# vidc_interposer1.net
KiCad netlist of a schematic drawn in EAGLE
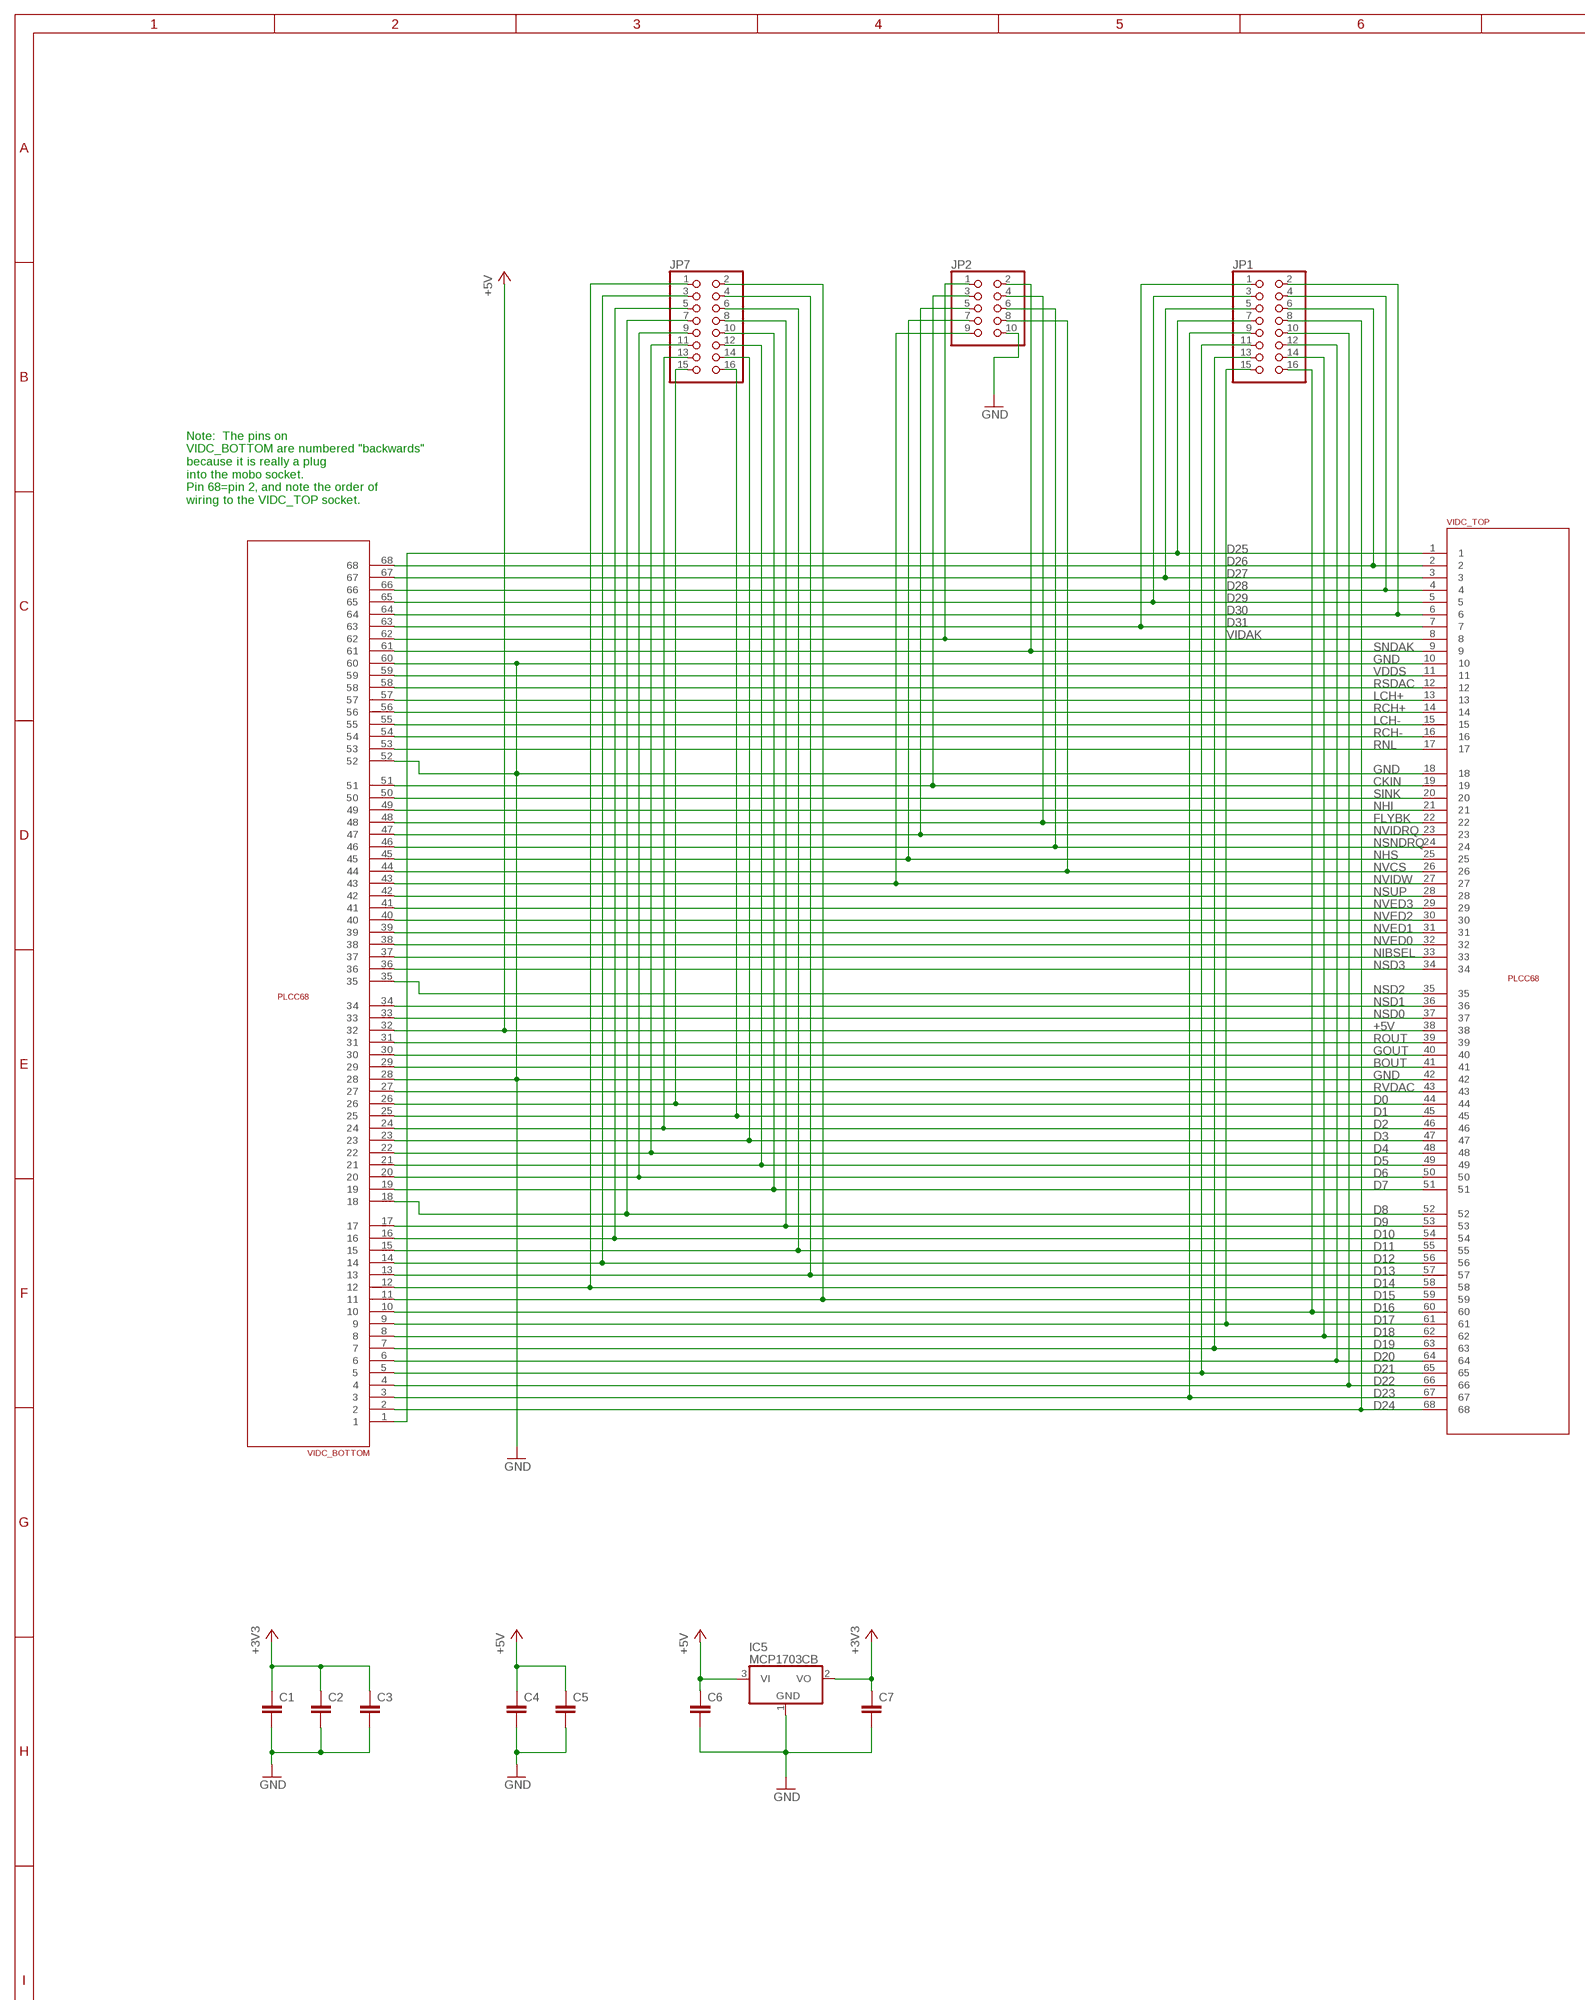
[diagram p0: schematic, sheet 1, part 1 of 2]
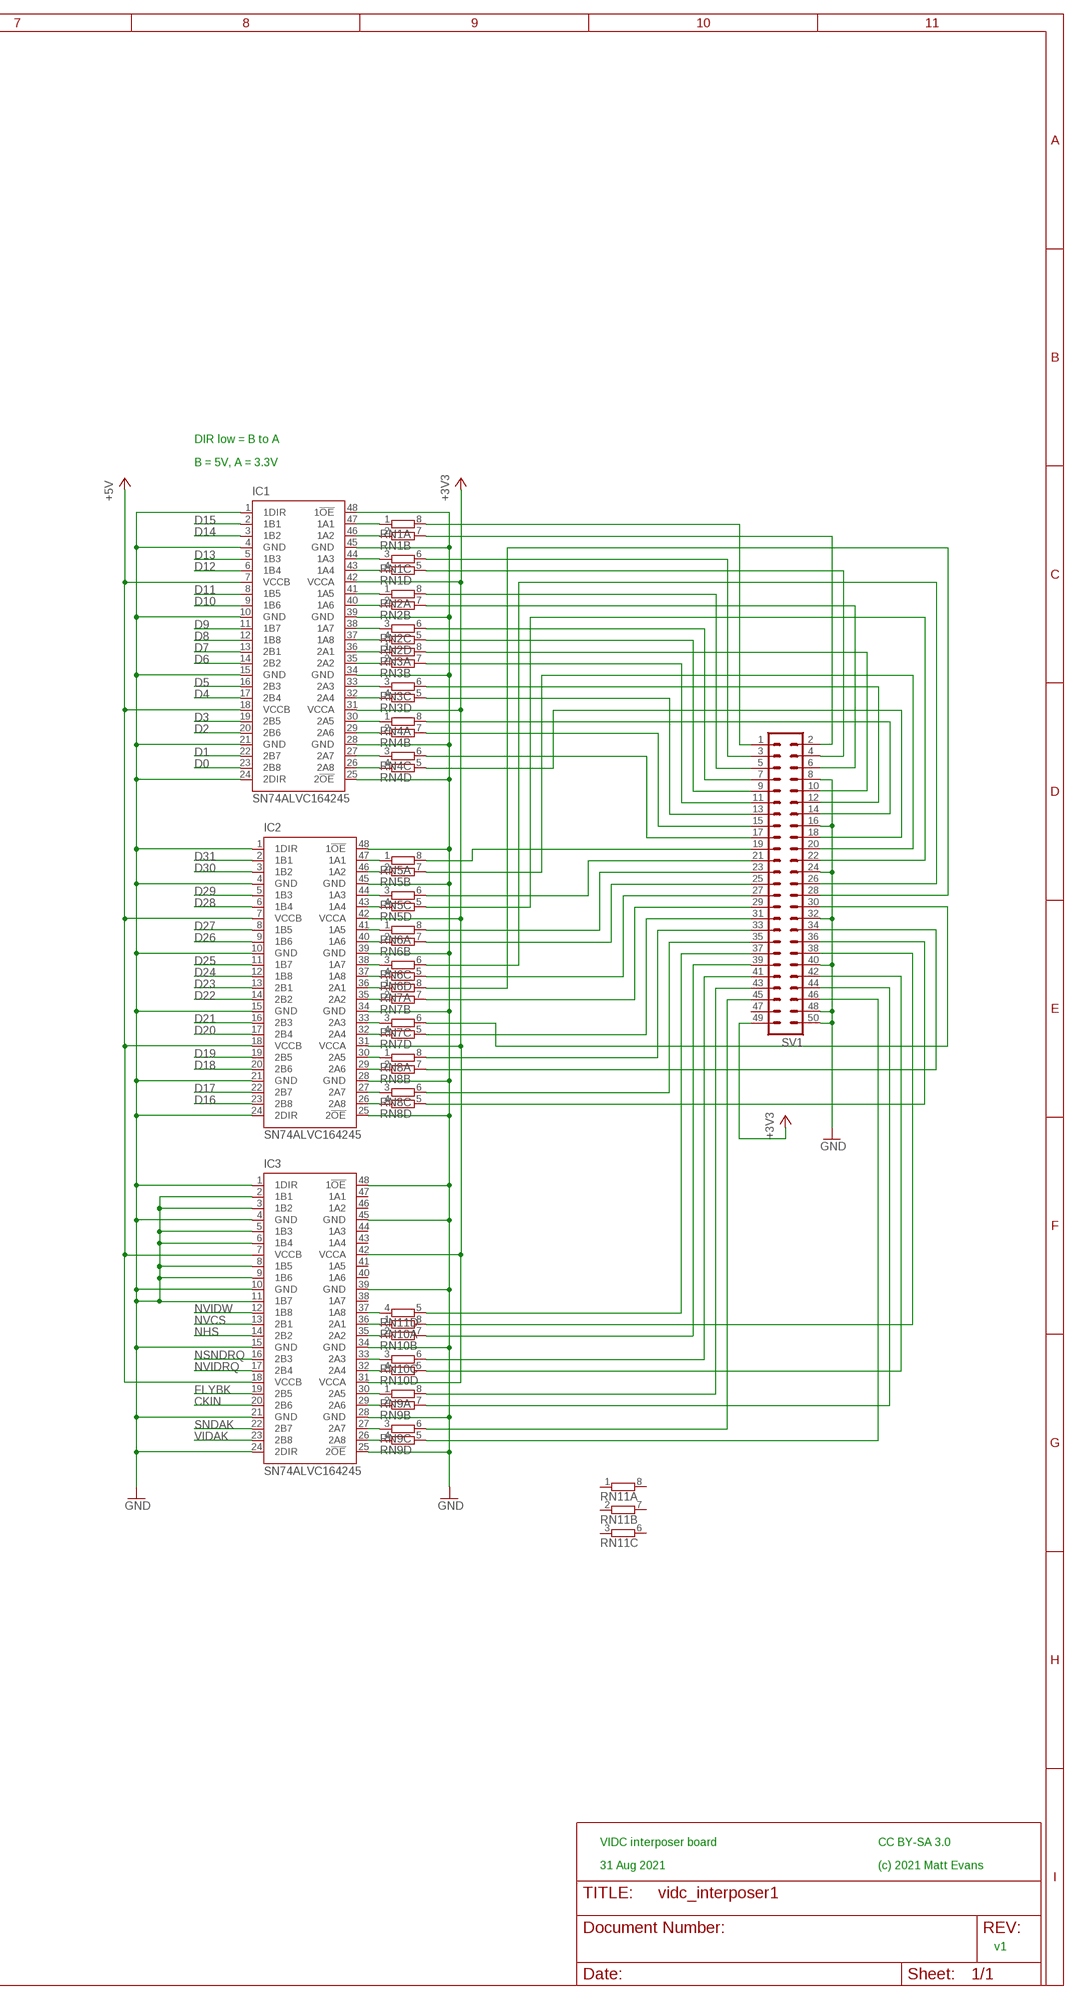
[diagram p1: schematic, sheet 1, part 2 of 2]

(export (version "E")
  (design (tool "Eeschema 10.0.6"))
  (components
    (comp (ref "C1")
      (value "C-EUC0805")
      (footprint "eagle-import:C0805")
      (libsource (lib "eagle-import") (part "C-EUC0805"))
    )
    (comp (ref "C2")
      (value "C-EUC0805")
      (footprint "eagle-import:C0805")
      (libsource (lib "eagle-import") (part "C-EUC0805"))
    )
    (comp (ref "C3")
      (value "C-EUC0805")
      (footprint "eagle-import:C0805")
      (libsource (lib "eagle-import") (part "C-EUC0805"))
    )
    (comp (ref "C4")
      (value "C-EUC0805")
      (footprint "eagle-import:C0805")
      (libsource (lib "eagle-import") (part "C-EUC0805"))
    )
    (comp (ref "C5")
      (value "C-EUC0805")
      (footprint "eagle-import:C0805")
      (libsource (lib "eagle-import") (part "C-EUC0805"))
    )
    (comp (ref "C6")
      (value "C-EUC0805")
      (footprint "eagle-import:C0805")
      (libsource (lib "eagle-import") (part "C-EUC0805"))
    )
    (comp (ref "C7")
      (value "C-EUC0805")
      (footprint "eagle-import:C0805")
      (libsource (lib "eagle-import") (part "C-EUC0805"))
    )
    (comp (ref "IC1")
      (value "SN74ALVC164245")
      (footprint "eagle-import:DL_R-PDSO-G48")
      (fields (field (name "MPN") "SN74LVCR162245DL"))
      (libsource (lib "eagle-import") (part "SN74ALVC164245"))
    )
    (comp (ref "IC2")
      (value "SN74ALVC164245")
      (footprint "eagle-import:DL_R-PDSO-G48")
      (fields (field (name "MPN") "SN74LVCR162245DL"))
      (libsource (lib "eagle-import") (part "SN74ALVC164245"))
    )
    (comp (ref "IC3")
      (value "SN74ALVC164245")
      (footprint "eagle-import:DL_R-PDSO-G48")
      (fields (field (name "MPN") "SN74LVCR162245DL"))
      (libsource (lib "eagle-import") (part "SN74ALVC164245"))
    )
    (comp (ref "IC5")
      (value "MCP1703CB")
      (footprint "eagle-import:SOT23")
      (libsource (lib "eagle-import") (part "MCP1703CB"))
    )
    (comp (ref "JP1")
      (value "PINHD-2X8")
      (footprint "eagle-import:2X08")
      (libsource (lib "eagle-import") (part "PINHD-2X8"))
    )
    (comp (ref "JP2")
      (value "PINHD-2X5")
      (footprint "eagle-import:2X05")
      (libsource (lib "eagle-import") (part "PINHD-2X5"))
    )
    (comp (ref "JP7")
      (value "PINHD-2X8")
      (footprint "eagle-import:2X08")
      (libsource (lib "eagle-import") (part "PINHD-2X8"))
    )
    (comp (ref "RN1")
      (value "4R-NCAY16")
      (footprint "eagle-import:CAY16")
      (libsource (lib "eagle-import") (part "4R-NCAY16"))
    )
    (comp (ref "RN2")
      (value "4R-NCAY16")
      (footprint "eagle-import:CAY16")
      (libsource (lib "eagle-import") (part "4R-NCAY16"))
    )
    (comp (ref "RN3")
      (value "4R-NCAY16")
      (footprint "eagle-import:CAY16")
      (libsource (lib "eagle-import") (part "4R-NCAY16"))
    )
    (comp (ref "RN4")
      (value "4R-NCAY16")
      (footprint "eagle-import:CAY16")
      (libsource (lib "eagle-import") (part "4R-NCAY16"))
    )
    (comp (ref "RN5")
      (value "4R-NCAY16")
      (footprint "eagle-import:CAY16")
      (libsource (lib "eagle-import") (part "4R-NCAY16"))
    )
    (comp (ref "RN6")
      (value "4R-NCAY16")
      (footprint "eagle-import:CAY16")
      (libsource (lib "eagle-import") (part "4R-NCAY16"))
    )
    (comp (ref "RN7")
      (value "4R-NCAY16")
      (footprint "eagle-import:CAY16")
      (libsource (lib "eagle-import") (part "4R-NCAY16"))
    )
    (comp (ref "RN8")
      (value "4R-NCAY16")
      (footprint "eagle-import:CAY16")
      (libsource (lib "eagle-import") (part "4R-NCAY16"))
    )
    (comp (ref "RN9")
      (value "4R-NCAY16")
      (footprint "eagle-import:CAY16")
      (libsource (lib "eagle-import") (part "4R-NCAY16"))
    )
    (comp (ref "RN10")
      (value "4R-NCAY16")
      (footprint "eagle-import:CAY16")
      (libsource (lib "eagle-import") (part "4R-NCAY16"))
    )
    (comp (ref "RN11")
      (value "4R-NCAY16")
      (footprint "eagle-import:CAY16")
      (libsource (lib "eagle-import") (part "4R-NCAY16"))
    )
    (comp (ref "SV1")
      (value "ML50")
      (footprint "eagle-import:ML50")
      (libsource (lib "eagle-import") (part "ML50"))
    )
    (comp (ref "VIDC_BOTTOM")
      (value "RAW_PLCC68")
      (footprint "eagle-import:PLCC68S")
      (libsource (lib "eagle-import") (part "RAW_PLCC68"))
    )
    (comp (ref "VIDC_TOP")
      (value "RAW_PLCC68")
      (footprint "eagle-import:PLCC68S")
      (libsource (lib "eagle-import") (part "RAW_PLCC68"))
    )
  )
  (nets
    (net (code "1") (name "+3V3") (class "Default")
      (node (ref "C1") (pin "1") (pinfunction "1_1") (pintype "passive"))
      (node (ref "C2") (pin "1") (pinfunction "1_1") (pintype "passive"))
      (node (ref "C3") (pin "1") (pinfunction "1_1") (pintype "passive"))
      (node (ref "C7") (pin "1") (pinfunction "1_1") (pintype "passive"))
      (node (ref "IC1") (pin "31") (pinfunction "VCCA_31") (pintype "power_in"))
      (node (ref "IC1") (pin "42") (pinfunction "VCCA_42") (pintype "power_in"))
      (node (ref "IC2") (pin "31") (pinfunction "VCCA_31") (pintype "power_in"))
      (node (ref "IC2") (pin "42") (pinfunction "VCCA_42") (pintype "power_in"))
      (node (ref "IC3") (pin "31") (pinfunction "VCCA_31") (pintype "power_in"))
      (node (ref "IC3") (pin "42") (pinfunction "VCCA_42") (pintype "power_in"))
      (node (ref "IC5") (pin "2") (pinfunction "VO_2") (pintype "passive"))
      (node (ref "SV1") (pin "49") (pinfunction "49_49") (pintype "passive"))
    )
    (net (code "2") (name "+5V") (class "Default")
      (node (ref "C4") (pin "1") (pinfunction "1_1") (pintype "passive"))
      (node (ref "C5") (pin "1") (pinfunction "1_1") (pintype "passive"))
      (node (ref "C6") (pin "1") (pinfunction "1_1") (pintype "passive"))
      (node (ref "IC1") (pin "18") (pinfunction "VCCB_18") (pintype "power_in"))
      (node (ref "IC1") (pin "7") (pinfunction "VCCB_7") (pintype "power_in"))
      (node (ref "IC2") (pin "18") (pinfunction "VCCB_18") (pintype "power_in"))
      (node (ref "IC2") (pin "7") (pinfunction "VCCB_7") (pintype "power_in"))
      (node (ref "IC3") (pin "18") (pinfunction "VCCB_18") (pintype "power_in"))
      (node (ref "IC3") (pin "7") (pinfunction "VCCB_7") (pintype "power_in"))
      (node (ref "IC5") (pin "3") (pinfunction "VI_3") (pintype "input"))
      (node (ref "VIDC_BOTTOM") (pin "32") (pinfunction "32_32") (pintype "bidirectional"))
      (node (ref "VIDC_TOP") (pin "38") (pinfunction "38_38") (pintype "bidirectional"))
    )
    (net (code "3") (name "/BOUT") (class "Default")
      (node (ref "VIDC_BOTTOM") (pin "29") (pinfunction "29_29") (pintype "bidirectional"))
      (node (ref "VIDC_TOP") (pin "41") (pinfunction "41_41") (pintype "bidirectional"))
    )
    (net (code "4") (name "/CKIN") (class "Default")
      (node (ref "IC3") (pin "20") (pinfunction "2B6_20") (pintype "tri_state"))
      (node (ref "JP2") (pin "3") (pinfunction "3_3") (pintype "passive"))
      (node (ref "VIDC_BOTTOM") (pin "51") (pinfunction "51_51") (pintype "bidirectional"))
      (node (ref "VIDC_TOP") (pin "19") (pinfunction "19_19") (pintype "bidirectional"))
    )
    (net (code "5") (name "/D0") (class "Default")
      (node (ref "IC1") (pin "23") (pinfunction "2B8_23") (pintype "tri_state"))
      (node (ref "JP7") (pin "15") (pinfunction "15_15") (pintype "passive"))
      (node (ref "VIDC_BOTTOM") (pin "26") (pinfunction "26_26") (pintype "bidirectional"))
      (node (ref "VIDC_TOP") (pin "44") (pinfunction "44_44") (pintype "bidirectional"))
    )
    (net (code "6") (name "/D1") (class "Default")
      (node (ref "IC1") (pin "22") (pinfunction "2B7_22") (pintype "tri_state"))
      (node (ref "JP7") (pin "16") (pinfunction "16_16") (pintype "passive"))
      (node (ref "VIDC_BOTTOM") (pin "25") (pinfunction "25_25") (pintype "bidirectional"))
      (node (ref "VIDC_TOP") (pin "45") (pinfunction "45_45") (pintype "bidirectional"))
    )
    (net (code "7") (name "/D2") (class "Default")
      (node (ref "IC1") (pin "20") (pinfunction "2B6_20") (pintype "tri_state"))
      (node (ref "JP7") (pin "13") (pinfunction "13_13") (pintype "passive"))
      (node (ref "VIDC_BOTTOM") (pin "24") (pinfunction "24_24") (pintype "bidirectional"))
      (node (ref "VIDC_TOP") (pin "46") (pinfunction "46_46") (pintype "bidirectional"))
    )
    (net (code "8") (name "/D3") (class "Default")
      (node (ref "IC1") (pin "19") (pinfunction "2B5_19") (pintype "tri_state"))
      (node (ref "JP7") (pin "14") (pinfunction "14_14") (pintype "passive"))
      (node (ref "VIDC_BOTTOM") (pin "23") (pinfunction "23_23") (pintype "bidirectional"))
      (node (ref "VIDC_TOP") (pin "47") (pinfunction "47_47") (pintype "bidirectional"))
    )
    (net (code "9") (name "/D4") (class "Default")
      (node (ref "IC1") (pin "17") (pinfunction "2B4_17") (pintype "tri_state"))
      (node (ref "JP7") (pin "11") (pinfunction "11_11") (pintype "passive"))
      (node (ref "VIDC_BOTTOM") (pin "22") (pinfunction "22_22") (pintype "bidirectional"))
      (node (ref "VIDC_TOP") (pin "48") (pinfunction "48_48") (pintype "bidirectional"))
    )
    (net (code "10") (name "/D5") (class "Default")
      (node (ref "IC1") (pin "16") (pinfunction "2B3_16") (pintype "tri_state"))
      (node (ref "JP7") (pin "12") (pinfunction "12_12") (pintype "passive"))
      (node (ref "VIDC_BOTTOM") (pin "21") (pinfunction "21_21") (pintype "bidirectional"))
      (node (ref "VIDC_TOP") (pin "49") (pinfunction "49_49") (pintype "bidirectional"))
    )
    (net (code "11") (name "/D6") (class "Default")
      (node (ref "IC1") (pin "14") (pinfunction "2B2_14") (pintype "tri_state"))
      (node (ref "JP7") (pin "9") (pinfunction "9_9") (pintype "passive"))
      (node (ref "VIDC_BOTTOM") (pin "20") (pinfunction "20_20") (pintype "bidirectional"))
      (node (ref "VIDC_TOP") (pin "50") (pinfunction "50_50") (pintype "bidirectional"))
    )
    (net (code "12") (name "/D7") (class "Default")
      (node (ref "IC1") (pin "13") (pinfunction "2B1_13") (pintype "tri_state"))
      (node (ref "JP7") (pin "10") (pinfunction "10_10") (pintype "passive"))
      (node (ref "VIDC_BOTTOM") (pin "19") (pinfunction "19_19") (pintype "bidirectional"))
      (node (ref "VIDC_TOP") (pin "51") (pinfunction "51_51") (pintype "bidirectional"))
    )
    (net (code "13") (name "/D8") (class "Default")
      (node (ref "IC1") (pin "12") (pinfunction "1B8_12") (pintype "tri_state"))
      (node (ref "JP7") (pin "7") (pinfunction "7_7") (pintype "passive"))
      (node (ref "VIDC_BOTTOM") (pin "18") (pinfunction "18_18") (pintype "bidirectional"))
      (node (ref "VIDC_TOP") (pin "52") (pinfunction "52_52") (pintype "bidirectional"))
    )
    (net (code "14") (name "/D9") (class "Default")
      (node (ref "IC1") (pin "11") (pinfunction "1B7_11") (pintype "tri_state"))
      (node (ref "JP7") (pin "8") (pinfunction "8_8") (pintype "passive"))
      (node (ref "VIDC_BOTTOM") (pin "17") (pinfunction "17_17") (pintype "bidirectional"))
      (node (ref "VIDC_TOP") (pin "53") (pinfunction "53_53") (pintype "bidirectional"))
    )
    (net (code "15") (name "/D10") (class "Default")
      (node (ref "IC1") (pin "9") (pinfunction "1B6_9") (pintype "tri_state"))
      (node (ref "JP7") (pin "5") (pinfunction "5_5") (pintype "passive"))
      (node (ref "VIDC_BOTTOM") (pin "16") (pinfunction "16_16") (pintype "bidirectional"))
      (node (ref "VIDC_TOP") (pin "54") (pinfunction "54_54") (pintype "bidirectional"))
    )
    (net (code "16") (name "/D11") (class "Default")
      (node (ref "IC1") (pin "8") (pinfunction "1B5_8") (pintype "tri_state"))
      (node (ref "JP7") (pin "6") (pinfunction "6_6") (pintype "passive"))
      (node (ref "VIDC_BOTTOM") (pin "15") (pinfunction "15_15") (pintype "bidirectional"))
      (node (ref "VIDC_TOP") (pin "55") (pinfunction "55_55") (pintype "bidirectional"))
    )
    (net (code "17") (name "/D12") (class "Default")
      (node (ref "IC1") (pin "6") (pinfunction "1B4_6") (pintype "tri_state"))
      (node (ref "JP7") (pin "3") (pinfunction "3_3") (pintype "passive"))
      (node (ref "VIDC_BOTTOM") (pin "14") (pinfunction "14_14") (pintype "bidirectional"))
      (node (ref "VIDC_TOP") (pin "56") (pinfunction "56_56") (pintype "bidirectional"))
    )
    (net (code "18") (name "/D13") (class "Default")
      (node (ref "IC1") (pin "5") (pinfunction "1B3_5") (pintype "tri_state"))
      (node (ref "JP7") (pin "4") (pinfunction "4_4") (pintype "passive"))
      (node (ref "VIDC_BOTTOM") (pin "13") (pinfunction "13_13") (pintype "bidirectional"))
      (node (ref "VIDC_TOP") (pin "57") (pinfunction "57_57") (pintype "bidirectional"))
    )
    (net (code "19") (name "/D14") (class "Default")
      (node (ref "IC1") (pin "3") (pinfunction "1B2_3") (pintype "tri_state"))
      (node (ref "JP7") (pin "1") (pinfunction "1_1") (pintype "passive"))
      (node (ref "VIDC_BOTTOM") (pin "12") (pinfunction "12_12") (pintype "bidirectional"))
      (node (ref "VIDC_TOP") (pin "58") (pinfunction "58_58") (pintype "bidirectional"))
    )
    (net (code "20") (name "/D15") (class "Default")
      (node (ref "IC1") (pin "2") (pinfunction "1B1_2") (pintype "tri_state"))
      (node (ref "JP7") (pin "2") (pinfunction "2_2") (pintype "passive"))
      (node (ref "VIDC_BOTTOM") (pin "11") (pinfunction "11_11") (pintype "bidirectional"))
      (node (ref "VIDC_TOP") (pin "59") (pinfunction "59_59") (pintype "bidirectional"))
    )
    (net (code "21") (name "/D16") (class "Default")
      (node (ref "IC2") (pin "23") (pinfunction "2B8_23") (pintype "tri_state"))
      (node (ref "JP1") (pin "16") (pinfunction "16_16") (pintype "passive"))
      (node (ref "VIDC_BOTTOM") (pin "10") (pinfunction "10_10") (pintype "bidirectional"))
      (node (ref "VIDC_TOP") (pin "60") (pinfunction "60_60") (pintype "bidirectional"))
    )
    (net (code "22") (name "/D17") (class "Default")
      (node (ref "IC2") (pin "22") (pinfunction "2B7_22") (pintype "tri_state"))
      (node (ref "JP1") (pin "15") (pinfunction "15_15") (pintype "passive"))
      (node (ref "VIDC_BOTTOM") (pin "9") (pinfunction "9_9") (pintype "bidirectional"))
      (node (ref "VIDC_TOP") (pin "61") (pinfunction "61_61") (pintype "bidirectional"))
    )
    (net (code "23") (name "/D18") (class "Default")
      (node (ref "IC2") (pin "20") (pinfunction "2B6_20") (pintype "tri_state"))
      (node (ref "JP1") (pin "14") (pinfunction "14_14") (pintype "passive"))
      (node (ref "VIDC_BOTTOM") (pin "8") (pinfunction "8_8") (pintype "bidirectional"))
      (node (ref "VIDC_TOP") (pin "62") (pinfunction "62_62") (pintype "bidirectional"))
    )
    (net (code "24") (name "/D19") (class "Default")
      (node (ref "IC2") (pin "19") (pinfunction "2B5_19") (pintype "tri_state"))
      (node (ref "JP1") (pin "13") (pinfunction "13_13") (pintype "passive"))
      (node (ref "VIDC_BOTTOM") (pin "7") (pinfunction "7_7") (pintype "bidirectional"))
      (node (ref "VIDC_TOP") (pin "63") (pinfunction "63_63") (pintype "bidirectional"))
    )
    (net (code "25") (name "/D20") (class "Default")
      (node (ref "IC2") (pin "17") (pinfunction "2B4_17") (pintype "tri_state"))
      (node (ref "JP1") (pin "12") (pinfunction "12_12") (pintype "passive"))
      (node (ref "VIDC_BOTTOM") (pin "6") (pinfunction "6_6") (pintype "bidirectional"))
      (node (ref "VIDC_TOP") (pin "64") (pinfunction "64_64") (pintype "bidirectional"))
    )
    (net (code "26") (name "/D21") (class "Default")
      (node (ref "IC2") (pin "16") (pinfunction "2B3_16") (pintype "tri_state"))
      (node (ref "JP1") (pin "11") (pinfunction "11_11") (pintype "passive"))
      (node (ref "VIDC_BOTTOM") (pin "5") (pinfunction "5_5") (pintype "bidirectional"))
      (node (ref "VIDC_TOP") (pin "65") (pinfunction "65_65") (pintype "bidirectional"))
    )
    (net (code "27") (name "/D22") (class "Default")
      (node (ref "IC2") (pin "14") (pinfunction "2B2_14") (pintype "tri_state"))
      (node (ref "JP1") (pin "10") (pinfunction "10_10") (pintype "passive"))
      (node (ref "VIDC_BOTTOM") (pin "4") (pinfunction "4_4") (pintype "bidirectional"))
      (node (ref "VIDC_TOP") (pin "66") (pinfunction "66_66") (pintype "bidirectional"))
    )
    (net (code "28") (name "/D23") (class "Default")
      (node (ref "IC2") (pin "13") (pinfunction "2B1_13") (pintype "tri_state"))
      (node (ref "JP1") (pin "9") (pinfunction "9_9") (pintype "passive"))
      (node (ref "VIDC_BOTTOM") (pin "3") (pinfunction "3_3") (pintype "bidirectional"))
      (node (ref "VIDC_TOP") (pin "67") (pinfunction "67_67") (pintype "bidirectional"))
    )
    (net (code "29") (name "/D24") (class "Default")
      (node (ref "IC2") (pin "12") (pinfunction "1B8_12") (pintype "tri_state"))
      (node (ref "JP1") (pin "8") (pinfunction "8_8") (pintype "passive"))
      (node (ref "VIDC_BOTTOM") (pin "2") (pinfunction "2_2") (pintype "bidirectional"))
      (node (ref "VIDC_TOP") (pin "68") (pinfunction "68_68") (pintype "bidirectional"))
    )
    (net (code "30") (name "/D25") (class "Default")
      (node (ref "IC2") (pin "11") (pinfunction "1B7_11") (pintype "tri_state"))
      (node (ref "JP1") (pin "7") (pinfunction "7_7") (pintype "passive"))
      (node (ref "VIDC_BOTTOM") (pin "1") (pinfunction "1_1") (pintype "bidirectional"))
      (node (ref "VIDC_TOP") (pin "1") (pinfunction "1_1") (pintype "bidirectional"))
    )
    (net (code "31") (name "/D26") (class "Default")
      (node (ref "IC2") (pin "9") (pinfunction "1B6_9") (pintype "tri_state"))
      (node (ref "JP1") (pin "6") (pinfunction "6_6") (pintype "passive"))
      (node (ref "VIDC_BOTTOM") (pin "68") (pinfunction "68_68") (pintype "bidirectional"))
      (node (ref "VIDC_TOP") (pin "2") (pinfunction "2_2") (pintype "bidirectional"))
    )
    (net (code "32") (name "/D27") (class "Default")
      (node (ref "IC2") (pin "8") (pinfunction "1B5_8") (pintype "tri_state"))
      (node (ref "JP1") (pin "5") (pinfunction "5_5") (pintype "passive"))
      (node (ref "VIDC_BOTTOM") (pin "67") (pinfunction "67_67") (pintype "bidirectional"))
      (node (ref "VIDC_TOP") (pin "3") (pinfunction "3_3") (pintype "bidirectional"))
    )
    (net (code "33") (name "/D28") (class "Default")
      (node (ref "IC2") (pin "6") (pinfunction "1B4_6") (pintype "tri_state"))
      (node (ref "JP1") (pin "4") (pinfunction "4_4") (pintype "passive"))
      (node (ref "VIDC_BOTTOM") (pin "66") (pinfunction "66_66") (pintype "bidirectional"))
      (node (ref "VIDC_TOP") (pin "4") (pinfunction "4_4") (pintype "bidirectional"))
    )
    (net (code "34") (name "/D29") (class "Default")
      (node (ref "IC2") (pin "5") (pinfunction "1B3_5") (pintype "tri_state"))
      (node (ref "JP1") (pin "3") (pinfunction "3_3") (pintype "passive"))
      (node (ref "VIDC_BOTTOM") (pin "65") (pinfunction "65_65") (pintype "bidirectional"))
      (node (ref "VIDC_TOP") (pin "5") (pinfunction "5_5") (pintype "bidirectional"))
    )
    (net (code "35") (name "/D30") (class "Default")
      (node (ref "IC2") (pin "3") (pinfunction "1B2_3") (pintype "tri_state"))
      (node (ref "JP1") (pin "2") (pinfunction "2_2") (pintype "passive"))
      (node (ref "VIDC_BOTTOM") (pin "64") (pinfunction "64_64") (pintype "bidirectional"))
      (node (ref "VIDC_TOP") (pin "6") (pinfunction "6_6") (pintype "bidirectional"))
    )
    (net (code "36") (name "/D31") (class "Default")
      (node (ref "IC2") (pin "2") (pinfunction "1B1_2") (pintype "tri_state"))
      (node (ref "JP1") (pin "1") (pinfunction "1_1") (pintype "passive"))
      (node (ref "VIDC_BOTTOM") (pin "63") (pinfunction "63_63") (pintype "bidirectional"))
      (node (ref "VIDC_TOP") (pin "7") (pinfunction "7_7") (pintype "bidirectional"))
    )
    (net (code "37") (name "/FLYBK") (class "Default")
      (node (ref "IC3") (pin "19") (pinfunction "2B5_19") (pintype "tri_state"))
      (node (ref "JP2") (pin "4") (pinfunction "4_4") (pintype "passive"))
      (node (ref "VIDC_BOTTOM") (pin "48") (pinfunction "48_48") (pintype "bidirectional"))
      (node (ref "VIDC_TOP") (pin "22") (pinfunction "22_22") (pintype "bidirectional"))
    )
    (net (code "38") (name "/GOUT") (class "Default")
      (node (ref "VIDC_BOTTOM") (pin "30") (pinfunction "30_30") (pintype "bidirectional"))
      (node (ref "VIDC_TOP") (pin "40") (pinfunction "40_40") (pintype "bidirectional"))
    )
    (net (code "39") (name "/LCH+") (class "Default")
      (node (ref "VIDC_BOTTOM") (pin "57") (pinfunction "57_57") (pintype "bidirectional"))
      (node (ref "VIDC_TOP") (pin "13") (pinfunction "13_13") (pintype "bidirectional"))
    )
    (net (code "40") (name "/LCH-") (class "Default")
      (node (ref "VIDC_BOTTOM") (pin "55") (pinfunction "55_55") (pintype "bidirectional"))
      (node (ref "VIDC_TOP") (pin "15") (pinfunction "15_15") (pintype "bidirectional"))
    )
    (net (code "41") (name "/NHI") (class "Default")
      (node (ref "VIDC_BOTTOM") (pin "49") (pinfunction "49_49") (pintype "bidirectional"))
      (node (ref "VIDC_TOP") (pin "21") (pinfunction "21_21") (pintype "bidirectional"))
    )
    (net (code "42") (name "/NHS") (class "Default")
      (node (ref "IC3") (pin "14") (pinfunction "2B2_14") (pintype "tri_state"))
      (node (ref "JP2") (pin "7") (pinfunction "7_7") (pintype "passive"))
      (node (ref "VIDC_BOTTOM") (pin "45") (pinfunction "45_45") (pintype "bidirectional"))
      (node (ref "VIDC_TOP") (pin "25") (pinfunction "25_25") (pintype "bidirectional"))
    )
    (net (code "43") (name "/NIBSEL") (class "Default")
      (node (ref "VIDC_BOTTOM") (pin "37") (pinfunction "37_37") (pintype "bidirectional"))
      (node (ref "VIDC_TOP") (pin "33") (pinfunction "33_33") (pintype "bidirectional"))
    )
    (net (code "44") (name "/NSD0") (class "Default")
      (node (ref "VIDC_BOTTOM") (pin "33") (pinfunction "33_33") (pintype "bidirectional"))
      (node (ref "VIDC_TOP") (pin "37") (pinfunction "37_37") (pintype "bidirectional"))
    )
    (net (code "45") (name "/NSD1") (class "Default")
      (node (ref "VIDC_BOTTOM") (pin "34") (pinfunction "34_34") (pintype "bidirectional"))
      (node (ref "VIDC_TOP") (pin "36") (pinfunction "36_36") (pintype "bidirectional"))
    )
    (net (code "46") (name "/NSD2") (class "Default")
      (node (ref "VIDC_BOTTOM") (pin "35") (pinfunction "35_35") (pintype "bidirectional"))
      (node (ref "VIDC_TOP") (pin "35") (pinfunction "35_35") (pintype "bidirectional"))
    )
    (net (code "47") (name "/NSD3") (class "Default")
      (node (ref "VIDC_BOTTOM") (pin "36") (pinfunction "36_36") (pintype "bidirectional"))
      (node (ref "VIDC_TOP") (pin "34") (pinfunction "34_34") (pintype "bidirectional"))
    )
    (net (code "48") (name "/NSNDRQ") (class "Default")
      (node (ref "IC3") (pin "16") (pinfunction "2B3_16") (pintype "tri_state"))
      (node (ref "JP2") (pin "6") (pinfunction "6_6") (pintype "passive"))
      (node (ref "VIDC_BOTTOM") (pin "46") (pinfunction "46_46") (pintype "bidirectional"))
      (node (ref "VIDC_TOP") (pin "24") (pinfunction "24_24") (pintype "bidirectional"))
    )
    (net (code "49") (name "/NSUP") (class "Default")
      (node (ref "VIDC_BOTTOM") (pin "42") (pinfunction "42_42") (pintype "bidirectional"))
      (node (ref "VIDC_TOP") (pin "28") (pinfunction "28_28") (pintype "bidirectional"))
    )
    (net (code "50") (name "/NVCS") (class "Default")
      (node (ref "IC3") (pin "13") (pinfunction "2B1_13") (pintype "tri_state"))
      (node (ref "JP2") (pin "8") (pinfunction "8_8") (pintype "passive"))
      (node (ref "VIDC_BOTTOM") (pin "44") (pinfunction "44_44") (pintype "bidirectional"))
      (node (ref "VIDC_TOP") (pin "26") (pinfunction "26_26") (pintype "bidirectional"))
    )
    (net (code "51") (name "/NVED0") (class "Default")
      (node (ref "VIDC_BOTTOM") (pin "38") (pinfunction "38_38") (pintype "bidirectional"))
      (node (ref "VIDC_TOP") (pin "32") (pinfunction "32_32") (pintype "bidirectional"))
    )
    (net (code "52") (name "/NVED1") (class "Default")
      (node (ref "VIDC_BOTTOM") (pin "39") (pinfunction "39_39") (pintype "bidirectional"))
      (node (ref "VIDC_TOP") (pin "31") (pinfunction "31_31") (pintype "bidirectional"))
    )
    (net (code "53") (name "/NVED2") (class "Default")
      (node (ref "VIDC_BOTTOM") (pin "40") (pinfunction "40_40") (pintype "bidirectional"))
      (node (ref "VIDC_TOP") (pin "30") (pinfunction "30_30") (pintype "bidirectional"))
    )
    (net (code "54") (name "/NVED3") (class "Default")
      (node (ref "VIDC_BOTTOM") (pin "41") (pinfunction "41_41") (pintype "bidirectional"))
      (node (ref "VIDC_TOP") (pin "29") (pinfunction "29_29") (pintype "bidirectional"))
    )
    (net (code "55") (name "/NVIDRQ") (class "Default")
      (node (ref "IC3") (pin "17") (pinfunction "2B4_17") (pintype "tri_state"))
      (node (ref "JP2") (pin "5") (pinfunction "5_5") (pintype "passive"))
      (node (ref "VIDC_BOTTOM") (pin "47") (pinfunction "47_47") (pintype "bidirectional"))
      (node (ref "VIDC_TOP") (pin "23") (pinfunction "23_23") (pintype "bidirectional"))
    )
    (net (code "56") (name "/NVIDW") (class "Default")
      (node (ref "IC3") (pin "12") (pinfunction "1B8_12") (pintype "tri_state"))
      (node (ref "JP2") (pin "9") (pinfunction "9_9") (pintype "passive"))
      (node (ref "VIDC_BOTTOM") (pin "43") (pinfunction "43_43") (pintype "bidirectional"))
      (node (ref "VIDC_TOP") (pin "27") (pinfunction "27_27") (pintype "bidirectional"))
    )
    (net (code "57") (name "/RCH+") (class "Default")
      (node (ref "VIDC_BOTTOM") (pin "56") (pinfunction "56_56") (pintype "bidirectional"))
      (node (ref "VIDC_TOP") (pin "14") (pinfunction "14_14") (pintype "bidirectional"))
    )
    (net (code "58") (name "/RCH-") (class "Default")
      (node (ref "VIDC_BOTTOM") (pin "54") (pinfunction "54_54") (pintype "bidirectional"))
      (node (ref "VIDC_TOP") (pin "16") (pinfunction "16_16") (pintype "bidirectional"))
    )
    (net (code "59") (name "/RNL") (class "Default")
      (node (ref "VIDC_BOTTOM") (pin "53") (pinfunction "53_53") (pintype "bidirectional"))
      (node (ref "VIDC_TOP") (pin "17") (pinfunction "17_17") (pintype "bidirectional"))
    )
    (net (code "60") (name "/ROUT") (class "Default")
      (node (ref "VIDC_BOTTOM") (pin "31") (pinfunction "31_31") (pintype "bidirectional"))
      (node (ref "VIDC_TOP") (pin "39") (pinfunction "39_39") (pintype "bidirectional"))
    )
    (net (code "61") (name "/RSDAC") (class "Default")
      (node (ref "VIDC_BOTTOM") (pin "58") (pinfunction "58_58") (pintype "bidirectional"))
      (node (ref "VIDC_TOP") (pin "12") (pinfunction "12_12") (pintype "bidirectional"))
    )
    (net (code "62") (name "/RVDAC") (class "Default")
      (node (ref "VIDC_BOTTOM") (pin "27") (pinfunction "27_27") (pintype "bidirectional"))
      (node (ref "VIDC_TOP") (pin "43") (pinfunction "43_43") (pintype "bidirectional"))
    )
    (net (code "63") (name "/SINK") (class "Default")
      (node (ref "VIDC_BOTTOM") (pin "50") (pinfunction "50_50") (pintype "bidirectional"))
      (node (ref "VIDC_TOP") (pin "20") (pinfunction "20_20") (pintype "bidirectional"))
    )
    (net (code "64") (name "/SNDAK") (class "Default")
      (node (ref "IC3") (pin "22") (pinfunction "2B7_22") (pintype "tri_state"))
      (node (ref "JP2") (pin "2") (pinfunction "2_2") (pintype "passive"))
      (node (ref "VIDC_BOTTOM") (pin "61") (pinfunction "61_61") (pintype "bidirectional"))
      (node (ref "VIDC_TOP") (pin "9") (pinfunction "9_9") (pintype "bidirectional"))
    )
    (net (code "65") (name "/VDDS") (class "Default")
      (node (ref "VIDC_BOTTOM") (pin "59") (pinfunction "59_59") (pintype "bidirectional"))
      (node (ref "VIDC_TOP") (pin "11") (pinfunction "11_11") (pintype "bidirectional"))
    )
    (net (code "66") (name "/VIDAK") (class "Default")
      (node (ref "IC3") (pin "23") (pinfunction "2B8_23") (pintype "tri_state"))
      (node (ref "JP2") (pin "1") (pinfunction "1_1") (pintype "passive"))
      (node (ref "VIDC_BOTTOM") (pin "62") (pinfunction "62_62") (pintype "bidirectional"))
      (node (ref "VIDC_TOP") (pin "8") (pinfunction "8_8") (pintype "bidirectional"))
    )
    (net (code "67") (name "GND") (class "Default")
      (node (ref "C1") (pin "2") (pinfunction "2_2") (pintype "passive"))
      (node (ref "C2") (pin "2") (pinfunction "2_2") (pintype "passive"))
      (node (ref "C3") (pin "2") (pinfunction "2_2") (pintype "passive"))
      (node (ref "C4") (pin "2") (pinfunction "2_2") (pintype "passive"))
      (node (ref "C5") (pin "2") (pinfunction "2_2") (pintype "passive"))
      (node (ref "C6") (pin "2") (pinfunction "2_2") (pintype "passive"))
      (node (ref "C7") (pin "2") (pinfunction "2_2") (pintype "passive"))
      (node (ref "IC1") (pin "1") (pinfunction "1DIR_1") (pintype "input"))
      (node (ref "IC1") (pin "10") (pinfunction "GND_10") (pintype "power_in"))
      (node (ref "IC1") (pin "15") (pinfunction "GND_15") (pintype "power_in"))
      (node (ref "IC1") (pin "21") (pinfunction "GND_21") (pintype "tri_state"))
      (node (ref "IC1") (pin "24") (pinfunction "2DIR_24") (pintype "input"))
      (node (ref "IC1") (pin "25") (pinfunction "2~{OE}_25") (pintype "input"))
      (node (ref "IC1") (pin "28") (pinfunction "GND_28") (pintype "power_in"))
      (node (ref "IC1") (pin "34") (pinfunction "GND_34") (pintype "power_in"))
      (node (ref "IC1") (pin "39") (pinfunction "GND_39") (pintype "tri_state"))
      (node (ref "IC1") (pin "4") (pinfunction "GND_4") (pintype "power_in"))
      (node (ref "IC1") (pin "45") (pinfunction "GND_45") (pintype "power_in"))
      (node (ref "IC1") (pin "48") (pinfunction "1~{OE}_48") (pintype "input"))
      (node (ref "IC2") (pin "1") (pinfunction "1DIR_1") (pintype "input"))
      (node (ref "IC2") (pin "10") (pinfunction "GND_10") (pintype "power_in"))
      (node (ref "IC2") (pin "15") (pinfunction "GND_15") (pintype "power_in"))
      (node (ref "IC2") (pin "21") (pinfunction "GND_21") (pintype "tri_state"))
      (node (ref "IC2") (pin "24") (pinfunction "2DIR_24") (pintype "input"))
      (node (ref "IC2") (pin "25") (pinfunction "2~{OE}_25") (pintype "input"))
      (node (ref "IC2") (pin "28") (pinfunction "GND_28") (pintype "power_in"))
      (node (ref "IC2") (pin "34") (pinfunction "GND_34") (pintype "power_in"))
      (node (ref "IC2") (pin "39") (pinfunction "GND_39") (pintype "tri_state"))
      (node (ref "IC2") (pin "4") (pinfunction "GND_4") (pintype "power_in"))
      (node (ref "IC2") (pin "45") (pinfunction "GND_45") (pintype "power_in"))
      (node (ref "IC2") (pin "48") (pinfunction "1~{OE}_48") (pintype "input"))
      (node (ref "IC3") (pin "1") (pinfunction "1DIR_1") (pintype "input"))
      (node (ref "IC3") (pin "10") (pinfunction "GND_10") (pintype "power_in"))
      (node (ref "IC3") (pin "11") (pinfunction "1B7_11") (pintype "tri_state"))
      (node (ref "IC3") (pin "15") (pinfunction "GND_15") (pintype "power_in"))
      (node (ref "IC3") (pin "2") (pinfunction "1B1_2") (pintype "tri_state"))
      (node (ref "IC3") (pin "21") (pinfunction "GND_21") (pintype "tri_state"))
      (node (ref "IC3") (pin "24") (pinfunction "2DIR_24") (pintype "input"))
      (node (ref "IC3") (pin "25") (pinfunction "2~{OE}_25") (pintype "input"))
      (node (ref "IC3") (pin "28") (pinfunction "GND_28") (pintype "power_in"))
      (node (ref "IC3") (pin "3") (pinfunction "1B2_3") (pintype "tri_state"))
      (node (ref "IC3") (pin "34") (pinfunction "GND_34") (pintype "power_in"))
      (node (ref "IC3") (pin "39") (pinfunction "GND_39") (pintype "tri_state"))
      (node (ref "IC3") (pin "4") (pinfunction "GND_4") (pintype "power_in"))
      (node (ref "IC3") (pin "45") (pinfunction "GND_45") (pintype "power_in"))
      (node (ref "IC3") (pin "48") (pinfunction "1~{OE}_48") (pintype "input"))
      (node (ref "IC3") (pin "5") (pinfunction "1B3_5") (pintype "tri_state"))
      (node (ref "IC3") (pin "6") (pinfunction "1B4_6") (pintype "tri_state"))
      (node (ref "IC3") (pin "8") (pinfunction "1B5_8") (pintype "tri_state"))
      (node (ref "IC3") (pin "9") (pinfunction "1B6_9") (pintype "tri_state"))
      (node (ref "IC5") (pin "1") (pinfunction "GND_1") (pintype "passive"))
      (node (ref "JP2") (pin "10") (pinfunction "10_10") (pintype "passive"))
      (node (ref "SV1") (pin "16") (pinfunction "16_16") (pintype "passive"))
      (node (ref "SV1") (pin "24") (pinfunction "24_24") (pintype "passive"))
      (node (ref "SV1") (pin "32") (pinfunction "32_32") (pintype "passive"))
      (node (ref "SV1") (pin "40") (pinfunction "40_40") (pintype "passive"))
      (node (ref "SV1") (pin "48") (pinfunction "48_48") (pintype "passive"))
      (node (ref "SV1") (pin "50") (pinfunction "50_50") (pintype "passive"))
      (node (ref "SV1") (pin "8") (pinfunction "8_8") (pintype "passive"))
      (node (ref "VIDC_BOTTOM") (pin "28") (pinfunction "28_28") (pintype "bidirectional"))
      (node (ref "VIDC_BOTTOM") (pin "52") (pinfunction "52_52") (pintype "bidirectional"))
      (node (ref "VIDC_BOTTOM") (pin "60") (pinfunction "60_60") (pintype "bidirectional"))
      (node (ref "VIDC_TOP") (pin "10") (pinfunction "10_10") (pintype "bidirectional"))
      (node (ref "VIDC_TOP") (pin "18") (pinfunction "18_18") (pintype "bidirectional"))
      (node (ref "VIDC_TOP") (pin "42") (pinfunction "42_42") (pintype "bidirectional"))
    )
    (net (code "68") (name "Net-(IC1-1A1)") (class "Default")
      (node (ref "IC1") (pin "47") (pinfunction "1A1_47") (pintype "tri_state"))
      (node (ref "RN1") (pin "1") (pinfunction "1_1") (pintype "passive"))
    )
    (net (code "69") (name "Net-(IC1-1A2)") (class "Default")
      (node (ref "IC1") (pin "46") (pinfunction "1A2_46") (pintype "tri_state"))
      (node (ref "RN1") (pin "2") (pinfunction "1_2") (pintype "passive"))
    )
    (net (code "70") (name "Net-(IC1-1A3)") (class "Default")
      (node (ref "IC1") (pin "44") (pinfunction "1A3_44") (pintype "tri_state"))
      (node (ref "RN1") (pin "3") (pinfunction "1_3") (pintype "passive"))
    )
    (net (code "71") (name "Net-(IC1-1A4)") (class "Default")
      (node (ref "IC1") (pin "43") (pinfunction "1A4_43") (pintype "tri_state"))
      (node (ref "RN1") (pin "4") (pinfunction "1_4") (pintype "passive"))
    )
    (net (code "72") (name "Net-(IC1-1A5)") (class "Default")
      (node (ref "IC1") (pin "41") (pinfunction "1A5_41") (pintype "tri_state"))
      (node (ref "RN2") (pin "1") (pinfunction "1_1") (pintype "passive"))
    )
    (net (code "73") (name "Net-(IC1-1A6)") (class "Default")
      (node (ref "IC1") (pin "40") (pinfunction "1A6_40") (pintype "tri_state"))
      (node (ref "RN2") (pin "2") (pinfunction "1_2") (pintype "passive"))
    )
    (net (code "74") (name "Net-(IC1-1A7)") (class "Default")
      (node (ref "IC1") (pin "38") (pinfunction "1A7_38") (pintype "tri_state"))
      (node (ref "RN2") (pin "3") (pinfunction "1_3") (pintype "passive"))
    )
    (net (code "75") (name "Net-(IC1-1A8)") (class "Default")
      (node (ref "IC1") (pin "37") (pinfunction "1A8_37") (pintype "tri_state"))
      (node (ref "RN2") (pin "4") (pinfunction "1_4") (pintype "passive"))
    )
    (net (code "76") (name "Net-(IC1-2A1)") (class "Default")
      (node (ref "IC1") (pin "36") (pinfunction "2A1_36") (pintype "tri_state"))
      (node (ref "RN3") (pin "1") (pinfunction "1_1") (pintype "passive"))
    )
    (net (code "77") (name "Net-(IC1-2A2)") (class "Default")
      (node (ref "IC1") (pin "35") (pinfunction "2A2_35") (pintype "tri_state"))
      (node (ref "RN3") (pin "2") (pinfunction "1_2") (pintype "passive"))
    )
    (net (code "78") (name "Net-(IC1-2A3)") (class "Default")
      (node (ref "IC1") (pin "33") (pinfunction "2A3_33") (pintype "tri_state"))
      (node (ref "RN3") (pin "3") (pinfunction "1_3") (pintype "passive"))
    )
    (net (code "79") (name "Net-(IC1-2A4)") (class "Default")
      (node (ref "IC1") (pin "32") (pinfunction "2A4_32") (pintype "tri_state"))
      (node (ref "RN3") (pin "4") (pinfunction "1_4") (pintype "passive"))
    )
    (net (code "80") (name "Net-(IC1-2A5)") (class "Default")
      (node (ref "IC1") (pin "30") (pinfunction "2A5_30") (pintype "tri_state"))
      (node (ref "RN4") (pin "1") (pinfunction "1_1") (pintype "passive"))
    )
    (net (code "81") (name "Net-(IC1-2A6)") (class "Default")
      (node (ref "IC1") (pin "29") (pinfunction "2A6_29") (pintype "tri_state"))
      (node (ref "RN4") (pin "2") (pinfunction "1_2") (pintype "passive"))
    )
    (net (code "82") (name "Net-(IC1-2A7)") (class "Default")
      (node (ref "IC1") (pin "27") (pinfunction "2A7_27") (pintype "tri_state"))
      (node (ref "RN4") (pin "3") (pinfunction "1_3") (pintype "passive"))
    )
    (net (code "83") (name "Net-(IC1-2A8)") (class "Default")
      (node (ref "IC1") (pin "26") (pinfunction "2A8_26") (pintype "tri_state"))
      (node (ref "RN4") (pin "4") (pinfunction "1_4") (pintype "passive"))
    )
    (net (code "84") (name "Net-(IC2-1A1)") (class "Default")
      (node (ref "IC2") (pin "47") (pinfunction "1A1_47") (pintype "tri_state"))
      (node (ref "RN5") (pin "1") (pinfunction "1_1") (pintype "passive"))
    )
    (net (code "85") (name "Net-(IC2-1A2)") (class "Default")
      (node (ref "IC2") (pin "46") (pinfunction "1A2_46") (pintype "tri_state"))
      (node (ref "RN5") (pin "2") (pinfunction "1_2") (pintype "passive"))
    )
    (net (code "86") (name "Net-(IC2-1A3)") (class "Default")
      (node (ref "IC2") (pin "44") (pinfunction "1A3_44") (pintype "tri_state"))
      (node (ref "RN5") (pin "3") (pinfunction "1_3") (pintype "passive"))
    )
    (net (code "87") (name "Net-(IC2-1A4)") (class "Default")
      (node (ref "IC2") (pin "43") (pinfunction "1A4_43") (pintype "tri_state"))
      (node (ref "RN5") (pin "4") (pinfunction "1_4") (pintype "passive"))
    )
    (net (code "88") (name "Net-(IC2-1A5)") (class "Default")
      (node (ref "IC2") (pin "41") (pinfunction "1A5_41") (pintype "tri_state"))
      (node (ref "RN6") (pin "1") (pinfunction "1_1") (pintype "passive"))
    )
    (net (code "89") (name "Net-(IC2-1A6)") (class "Default")
      (node (ref "IC2") (pin "40") (pinfunction "1A6_40") (pintype "tri_state"))
      (node (ref "RN6") (pin "2") (pinfunction "1_2") (pintype "passive"))
    )
    (net (code "90") (name "Net-(IC2-1A7)") (class "Default")
      (node (ref "IC2") (pin "38") (pinfunction "1A7_38") (pintype "tri_state"))
      (node (ref "RN6") (pin "3") (pinfunction "1_3") (pintype "passive"))
    )
    (net (code "91") (name "Net-(IC2-1A8)") (class "Default")
      (node (ref "IC2") (pin "37") (pinfunction "1A8_37") (pintype "tri_state"))
      (node (ref "RN6") (pin "4") (pinfunction "1_4") (pintype "passive"))
    )
    (net (code "92") (name "Net-(IC2-2A1)") (class "Default")
      (node (ref "IC2") (pin "36") (pinfunction "2A1_36") (pintype "tri_state"))
      (node (ref "RN7") (pin "1") (pinfunction "1_1") (pintype "passive"))
    )
    (net (code "93") (name "Net-(IC2-2A2)") (class "Default")
      (node (ref "IC2") (pin "35") (pinfunction "2A2_35") (pintype "tri_state"))
      (node (ref "RN7") (pin "2") (pinfunction "1_2") (pintype "passive"))
    )
    (net (code "94") (name "Net-(IC2-2A3)") (class "Default")
      (node (ref "IC2") (pin "33") (pinfunction "2A3_33") (pintype "tri_state"))
      (node (ref "RN7") (pin "3") (pinfunction "1_3") (pintype "passive"))
    )
    (net (code "95") (name "Net-(IC2-2A4)") (class "Default")
      (node (ref "IC2") (pin "32") (pinfunction "2A4_32") (pintype "tri_state"))
      (node (ref "RN7") (pin "4") (pinfunction "1_4") (pintype "passive"))
    )
    (net (code "96") (name "Net-(IC2-2A5)") (class "Default")
      (node (ref "IC2") (pin "30") (pinfunction "2A5_30") (pintype "tri_state"))
      (node (ref "RN8") (pin "1") (pinfunction "1_1") (pintype "passive"))
    )
    (net (code "97") (name "Net-(IC2-2A6)") (class "Default")
      (node (ref "IC2") (pin "29") (pinfunction "2A6_29") (pintype "tri_state"))
      (node (ref "RN8") (pin "2") (pinfunction "1_2") (pintype "passive"))
    )
    (net (code "98") (name "Net-(IC2-2A7)") (class "Default")
      (node (ref "IC2") (pin "27") (pinfunction "2A7_27") (pintype "tri_state"))
      (node (ref "RN8") (pin "3") (pinfunction "1_3") (pintype "passive"))
    )
    (net (code "99") (name "Net-(IC2-2A8)") (class "Default")
      (node (ref "IC2") (pin "26") (pinfunction "2A8_26") (pintype "tri_state"))
      (node (ref "RN8") (pin "4") (pinfunction "1_4") (pintype "passive"))
    )
    (net (code "100") (name "Net-(IC3-1A8)") (class "Default")
      (node (ref "IC3") (pin "37") (pinfunction "1A8_37") (pintype "tri_state"))
      (node (ref "RN11") (pin "4") (pinfunction "1_4") (pintype "passive"))
    )
    (net (code "101") (name "Net-(IC3-2A1)") (class "Default")
      (node (ref "IC3") (pin "36") (pinfunction "2A1_36") (pintype "tri_state"))
      (node (ref "RN10") (pin "1") (pinfunction "1_1") (pintype "passive"))
    )
    (net (code "102") (name "Net-(IC3-2A2)") (class "Default")
      (node (ref "IC3") (pin "35") (pinfunction "2A2_35") (pintype "tri_state"))
      (node (ref "RN10") (pin "2") (pinfunction "1_2") (pintype "passive"))
    )
    (net (code "103") (name "Net-(IC3-2A3)") (class "Default")
      (node (ref "IC3") (pin "33") (pinfunction "2A3_33") (pintype "tri_state"))
      (node (ref "RN10") (pin "3") (pinfunction "1_3") (pintype "passive"))
    )
    (net (code "104") (name "Net-(IC3-2A4)") (class "Default")
      (node (ref "IC3") (pin "32") (pinfunction "2A4_32") (pintype "tri_state"))
      (node (ref "RN10") (pin "4") (pinfunction "1_4") (pintype "passive"))
    )
    (net (code "105") (name "Net-(IC3-2A5)") (class "Default")
      (node (ref "IC3") (pin "30") (pinfunction "2A5_30") (pintype "tri_state"))
      (node (ref "RN9") (pin "1") (pinfunction "1_1") (pintype "passive"))
    )
    (net (code "106") (name "Net-(IC3-2A6)") (class "Default")
      (node (ref "IC3") (pin "29") (pinfunction "2A6_29") (pintype "tri_state"))
      (node (ref "RN9") (pin "2") (pinfunction "1_2") (pintype "passive"))
    )
    (net (code "107") (name "Net-(IC3-2A7)") (class "Default")
      (node (ref "IC3") (pin "27") (pinfunction "2A7_27") (pintype "tri_state"))
      (node (ref "RN9") (pin "3") (pinfunction "1_3") (pintype "passive"))
    )
    (net (code "108") (name "Net-(IC3-2A8)") (class "Default")
      (node (ref "IC3") (pin "26") (pinfunction "2A8_26") (pintype "tri_state"))
      (node (ref "RN9") (pin "4") (pinfunction "1_4") (pintype "passive"))
    )
    (net (code "109") (name "Net-(RN1A-2)") (class "Default")
      (node (ref "RN1") (pin "8") (pinfunction "2_8") (pintype "passive"))
      (node (ref "SV1") (pin "1") (pinfunction "1_1") (pintype "passive"))
    )
    (net (code "110") (name "Net-(RN1B-2)") (class "Default")
      (node (ref "RN1") (pin "7") (pinfunction "2_7") (pintype "passive"))
      (node (ref "SV1") (pin "2") (pinfunction "2_2") (pintype "passive"))
    )
    (net (code "111") (name "Net-(RN1C-2)") (class "Default")
      (node (ref "RN1") (pin "6") (pinfunction "2_6") (pintype "passive"))
      (node (ref "SV1") (pin "3") (pinfunction "3_3") (pintype "passive"))
    )
    (net (code "112") (name "Net-(RN1D-2)") (class "Default")
      (node (ref "RN1") (pin "5") (pinfunction "2_5") (pintype "passive"))
      (node (ref "SV1") (pin "4") (pinfunction "4_4") (pintype "passive"))
    )
    (net (code "113") (name "Net-(RN2A-2)") (class "Default")
      (node (ref "RN2") (pin "8") (pinfunction "2_8") (pintype "passive"))
      (node (ref "SV1") (pin "5") (pinfunction "5_5") (pintype "passive"))
    )
    (net (code "114") (name "Net-(RN2B-2)") (class "Default")
      (node (ref "RN2") (pin "7") (pinfunction "2_7") (pintype "passive"))
      (node (ref "SV1") (pin "6") (pinfunction "6_6") (pintype "passive"))
    )
    (net (code "115") (name "Net-(RN2C-2)") (class "Default")
      (node (ref "RN2") (pin "6") (pinfunction "2_6") (pintype "passive"))
      (node (ref "SV1") (pin "7") (pinfunction "7_7") (pintype "passive"))
    )
    (net (code "116") (name "Net-(RN2D-2)") (class "Default")
      (node (ref "RN2") (pin "5") (pinfunction "2_5") (pintype "passive"))
      (node (ref "SV1") (pin "9") (pinfunction "9_9") (pintype "passive"))
    )
    (net (code "117") (name "Net-(RN3A-2)") (class "Default")
      (node (ref "RN3") (pin "8") (pinfunction "2_8") (pintype "passive"))
      (node (ref "SV1") (pin "10") (pinfunction "10_10") (pintype "passive"))
    )
    (net (code "118") (name "Net-(RN3B-2)") (class "Default")
      (node (ref "RN3") (pin "7") (pinfunction "2_7") (pintype "passive"))
      (node (ref "SV1") (pin "11") (pinfunction "11_11") (pintype "passive"))
    )
    (net (code "119") (name "Net-(RN3C-2)") (class "Default")
      (node (ref "RN3") (pin "6") (pinfunction "2_6") (pintype "passive"))
      (node (ref "SV1") (pin "12") (pinfunction "12_12") (pintype "passive"))
    )
    (net (code "120") (name "Net-(RN3D-2)") (class "Default")
      (node (ref "RN3") (pin "5") (pinfunction "2_5") (pintype "passive"))
      (node (ref "SV1") (pin "13") (pinfunction "13_13") (pintype "passive"))
    )
    (net (code "121") (name "Net-(RN4A-2)") (class "Default")
      (node (ref "RN4") (pin "8") (pinfunction "2_8") (pintype "passive"))
      (node (ref "SV1") (pin "14") (pinfunction "14_14") (pintype "passive"))
    )
    (net (code "122") (name "Net-(RN4B-2)") (class "Default")
      (node (ref "RN4") (pin "7") (pinfunction "2_7") (pintype "passive"))
      (node (ref "SV1") (pin "15") (pinfunction "15_15") (pintype "passive"))
    )
    (net (code "123") (name "Net-(RN4C-2)") (class "Default")
      (node (ref "RN4") (pin "6") (pinfunction "2_6") (pintype "passive"))
      (node (ref "SV1") (pin "17") (pinfunction "17_17") (pintype "passive"))
    )
    (net (code "124") (name "Net-(RN4D-2)") (class "Default")
      (node (ref "RN4") (pin "5") (pinfunction "2_5") (pintype "passive"))
      (node (ref "SV1") (pin "18") (pinfunction "18_18") (pintype "passive"))
    )
    (net (code "125") (name "Net-(RN5A-2)") (class "Default")
      (node (ref "RN5") (pin "8") (pinfunction "2_8") (pintype "passive"))
      (node (ref "SV1") (pin "19") (pinfunction "19_19") (pintype "passive"))
    )
    (net (code "126") (name "Net-(RN5B-2)") (class "Default")
      (node (ref "RN5") (pin "7") (pinfunction "2_7") (pintype "passive"))
      (node (ref "SV1") (pin "20") (pinfunction "20_20") (pintype "passive"))
    )
    (net (code "127") (name "Net-(RN5C-2)") (class "Default")
      (node (ref "RN5") (pin "6") (pinfunction "2_6") (pintype "passive"))
      (node (ref "SV1") (pin "21") (pinfunction "21_21") (pintype "passive"))
    )
    (net (code "128") (name "Net-(RN5D-2)") (class "Default")
      (node (ref "RN5") (pin "5") (pinfunction "2_5") (pintype "passive"))
      (node (ref "SV1") (pin "22") (pinfunction "22_22") (pintype "passive"))
    )
    (net (code "129") (name "Net-(RN6A-2)") (class "Default")
      (node (ref "RN6") (pin "8") (pinfunction "2_8") (pintype "passive"))
      (node (ref "SV1") (pin "23") (pinfunction "23_23") (pintype "passive"))
    )
    (net (code "130") (name "Net-(RN6B-2)") (class "Default")
      (node (ref "RN6") (pin "7") (pinfunction "2_7") (pintype "passive"))
      (node (ref "SV1") (pin "25") (pinfunction "25_25") (pintype "passive"))
    )
    (net (code "131") (name "Net-(RN6C-2)") (class "Default")
      (node (ref "RN6") (pin "6") (pinfunction "2_6") (pintype "passive"))
      (node (ref "SV1") (pin "26") (pinfunction "26_26") (pintype "passive"))
    )
    (net (code "132") (name "Net-(RN6D-2)") (class "Default")
      (node (ref "RN6") (pin "5") (pinfunction "2_5") (pintype "passive"))
      (node (ref "SV1") (pin "27") (pinfunction "27_27") (pintype "passive"))
    )
    (net (code "133") (name "Net-(RN7A-2)") (class "Default")
      (node (ref "RN7") (pin "8") (pinfunction "2_8") (pintype "passive"))
      (node (ref "SV1") (pin "28") (pinfunction "28_28") (pintype "passive"))
    )
    (net (code "134") (name "Net-(RN7B-2)") (class "Default")
      (node (ref "RN7") (pin "7") (pinfunction "2_7") (pintype "passive"))
      (node (ref "SV1") (pin "29") (pinfunction "29_29") (pintype "passive"))
    )
    (net (code "135") (name "Net-(RN7C-2)") (class "Default")
      (node (ref "RN7") (pin "6") (pinfunction "2_6") (pintype "passive"))
      (node (ref "SV1") (pin "30") (pinfunction "30_30") (pintype "passive"))
    )
    (net (code "136") (name "Net-(RN7D-2)") (class "Default")
      (node (ref "RN7") (pin "5") (pinfunction "2_5") (pintype "passive"))
      (node (ref "SV1") (pin "31") (pinfunction "31_31") (pintype "passive"))
    )
    (net (code "137") (name "Net-(RN8A-2)") (class "Default")
      (node (ref "RN8") (pin "8") (pinfunction "2_8") (pintype "passive"))
      (node (ref "SV1") (pin "33") (pinfunction "33_33") (pintype "passive"))
    )
    (net (code "138") (name "Net-(RN8B-2)") (class "Default")
      (node (ref "RN8") (pin "7") (pinfunction "2_7") (pintype "passive"))
      (node (ref "SV1") (pin "34") (pinfunction "34_34") (pintype "passive"))
    )
    (net (code "139") (name "Net-(RN8C-2)") (class "Default")
      (node (ref "RN8") (pin "6") (pinfunction "2_6") (pintype "passive"))
      (node (ref "SV1") (pin "35") (pinfunction "35_35") (pintype "passive"))
    )
    (net (code "140") (name "Net-(RN8D-2)") (class "Default")
      (node (ref "RN8") (pin "5") (pinfunction "2_5") (pintype "passive"))
      (node (ref "SV1") (pin "36") (pinfunction "36_36") (pintype "passive"))
    )
    (net (code "141") (name "Net-(RN9A-2)") (class "Default")
      (node (ref "RN9") (pin "8") (pinfunction "2_8") (pintype "passive"))
      (node (ref "SV1") (pin "43") (pinfunction "43_43") (pintype "passive"))
    )
    (net (code "142") (name "Net-(RN9B-2)") (class "Default")
      (node (ref "RN9") (pin "7") (pinfunction "2_7") (pintype "passive"))
      (node (ref "SV1") (pin "44") (pinfunction "44_44") (pintype "passive"))
    )
    (net (code "143") (name "Net-(RN9C-2)") (class "Default")
      (node (ref "RN9") (pin "6") (pinfunction "2_6") (pintype "passive"))
      (node (ref "SV1") (pin "45") (pinfunction "45_45") (pintype "passive"))
    )
    (net (code "144") (name "Net-(RN9D-2)") (class "Default")
      (node (ref "RN9") (pin "5") (pinfunction "2_5") (pintype "passive"))
      (node (ref "SV1") (pin "46") (pinfunction "46_46") (pintype "passive"))
    )
    (net (code "145") (name "Net-(RN10A-2)") (class "Default")
      (node (ref "RN10") (pin "8") (pinfunction "2_8") (pintype "passive"))
      (node (ref "SV1") (pin "38") (pinfunction "38_38") (pintype "passive"))
    )
    (net (code "146") (name "Net-(RN10B-2)") (class "Default")
      (node (ref "RN10") (pin "7") (pinfunction "2_7") (pintype "passive"))
      (node (ref "SV1") (pin "39") (pinfunction "39_39") (pintype "passive"))
    )
    (net (code "147") (name "Net-(RN10C-2)") (class "Default")
      (node (ref "RN10") (pin "6") (pinfunction "2_6") (pintype "passive"))
      (node (ref "SV1") (pin "41") (pinfunction "41_41") (pintype "passive"))
    )
    (net (code "148") (name "Net-(RN10D-2)") (class "Default")
      (node (ref "RN10") (pin "5") (pinfunction "2_5") (pintype "passive"))
      (node (ref "SV1") (pin "42") (pinfunction "42_42") (pintype "passive"))
    )
    (net (code "149") (name "Net-(RN11D-2)") (class "Default")
      (node (ref "RN11") (pin "5") (pinfunction "2_5") (pintype "passive"))
      (node (ref "SV1") (pin "37") (pinfunction "37_37") (pintype "passive"))
    )
    (net (code "150") (name "unconnected-(IC3-1A1-Pad47)") (class "Default")
      (node (ref "IC3") (pin "47") (pinfunction "1A1_47") (pintype "tri_state"))
    )
    (net (code "151") (name "unconnected-(IC3-1A2-Pad46)") (class "Default")
      (node (ref "IC3") (pin "46") (pinfunction "1A2_46") (pintype "tri_state"))
    )
    (net (code "152") (name "unconnected-(IC3-1A3-Pad44)") (class "Default")
      (node (ref "IC3") (pin "44") (pinfunction "1A3_44") (pintype "tri_state"))
    )
    (net (code "153") (name "unconnected-(IC3-1A4-Pad43)") (class "Default")
      (node (ref "IC3") (pin "43") (pinfunction "1A4_43") (pintype "tri_state"))
    )
    (net (code "154") (name "unconnected-(IC3-1A5-Pad41)") (class "Default")
      (node (ref "IC3") (pin "41") (pinfunction "1A5_41") (pintype "tri_state"))
    )
    (net (code "155") (name "unconnected-(IC3-1A6-Pad40)") (class "Default")
      (node (ref "IC3") (pin "40") (pinfunction "1A6_40") (pintype "tri_state"))
    )
    (net (code "156") (name "unconnected-(IC3-1A7-Pad38)") (class "Default")
      (node (ref "IC3") (pin "38") (pinfunction "1A7_38") (pintype "tri_state"))
    )
    (net (code "157") (name "unconnected-(RN11-Pad1)") (class "Default")
      (node (ref "RN11") (pin "1") (pinfunction "1_1") (pintype "passive"))
    )
    (net (code "158") (name "unconnected-(RN11A-2-Pad8)") (class "Default")
      (node (ref "RN11") (pin "8") (pinfunction "2_8") (pintype "passive"))
    )
    (net (code "159") (name "unconnected-(RN11B-1-Pad2)") (class "Default")
      (node (ref "RN11") (pin "2") (pinfunction "1_2") (pintype "passive"))
    )
    (net (code "160") (name "unconnected-(RN11B-2-Pad7)") (class "Default")
      (node (ref "RN11") (pin "7") (pinfunction "2_7") (pintype "passive"))
    )
    (net (code "161") (name "unconnected-(RN11C-1-Pad3)") (class "Default")
      (node (ref "RN11") (pin "3") (pinfunction "1_3") (pintype "passive"))
    )
    (net (code "162") (name "unconnected-(RN11C-2-Pad6)") (class "Default")
      (node (ref "RN11") (pin "6") (pinfunction "2_6") (pintype "passive"))
    )
    (net (code "163") (name "unconnected-(SV1-Pad47)") (class "Default")
      (node (ref "SV1") (pin "47") (pinfunction "47_47") (pintype "passive"))
    )
  )
)
